# Bus_Definition_V1_22.net
KiCad netlist of a schematic drawn in EAGLE
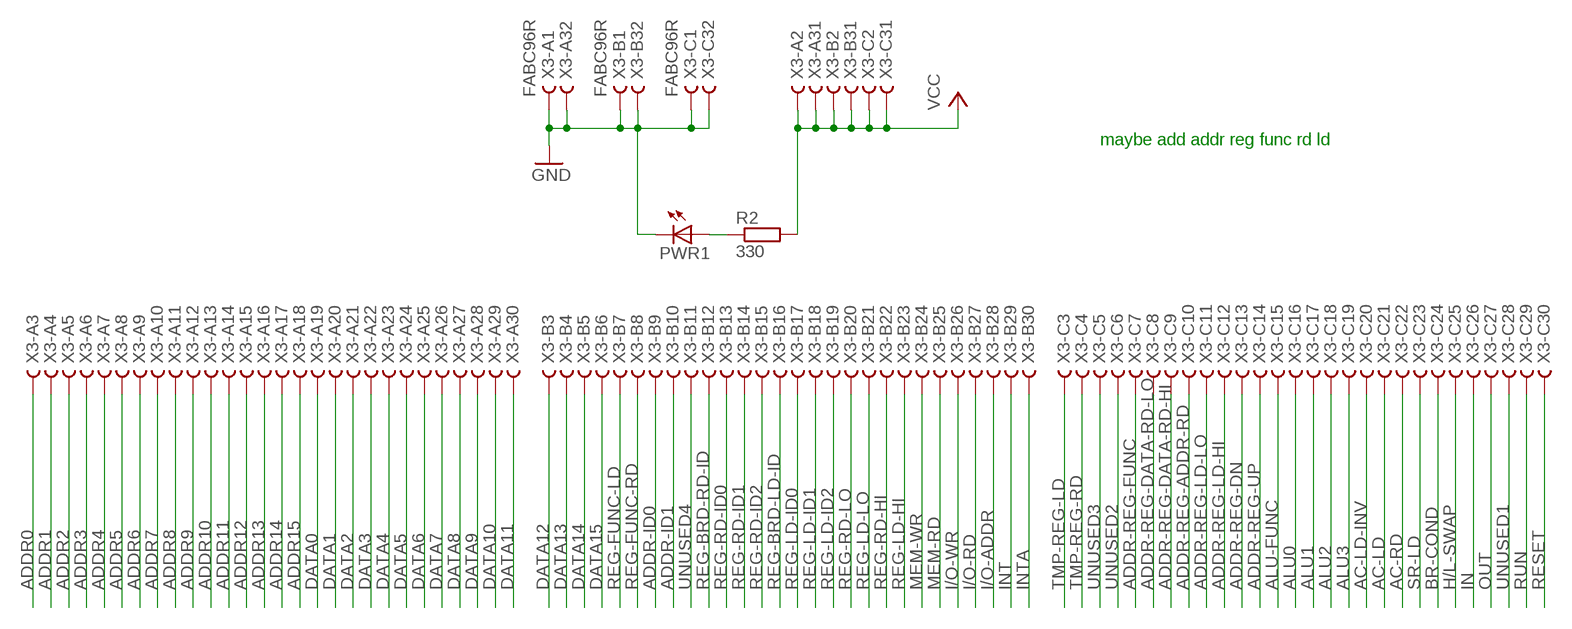
[diagram p0: schematic, sheet 1]

(export (version "E")
  (design (tool "Eeschema 10.0.6"))
  (components
    (comp (ref "PWR1")
      (value "LED5MM")
      (footprint "eagle-import:LED5MM")
      (libsource (lib "eagle-import") (part "LED5MM"))
    )
    (comp (ref "R2")
      (value "330")
      (footprint "eagle-import:0207_10")
      (libsource (lib "eagle-import") (part "R0207/10"))
    )
    (comp (ref "X3")
      (value "FABC96R")
      (footprint "eagle-import:FABC96R")
      (libsource (lib "eagle-import") (part "FABC96R"))
    )
  )
  (nets
    (net (code "1") (name "/AC-LD") (class "Default")
      (node (ref "X3") (pin "C21") (pinfunction "B_C21") (pintype "passive"))
    )
    (net (code "2") (name "/AC-LD-INV") (class "Default")
      (node (ref "X3") (pin "C20") (pinfunction "B_C20") (pintype "passive"))
    )
    (net (code "3") (name "/AC-RD") (class "Default")
      (node (ref "X3") (pin "C22") (pinfunction "B_C22") (pintype "passive"))
    )
    (net (code "4") (name "/ADDR-ID0") (class "Default")
      (node (ref "X3") (pin "B9") (pinfunction "B_B9") (pintype "passive"))
    )
    (net (code "5") (name "/ADDR-ID1") (class "Default")
      (node (ref "X3") (pin "B10") (pinfunction "B_B10") (pintype "passive"))
    )
    (net (code "6") (name "/ADDR-REG-ADDR-RD") (class "Default")
      (node (ref "X3") (pin "C10") (pinfunction "B_C10") (pintype "passive"))
    )
    (net (code "7") (name "/ADDR-REG-DATA-RD-HI") (class "Default")
      (node (ref "X3") (pin "C9") (pinfunction "B_C9") (pintype "passive"))
    )
    (net (code "8") (name "/ADDR-REG-DATA-RD-LO") (class "Default")
      (node (ref "X3") (pin "C8") (pinfunction "B_C8") (pintype "passive"))
    )
    (net (code "9") (name "/ADDR-REG-DN") (class "Default")
      (node (ref "X3") (pin "C13") (pinfunction "B_C13") (pintype "passive"))
    )
    (net (code "10") (name "/ADDR-REG-FUNC") (class "Default")
      (node (ref "X3") (pin "C7") (pinfunction "B_C7") (pintype "passive"))
    )
    (net (code "11") (name "/ADDR-REG-LD-HI") (class "Default")
      (node (ref "X3") (pin "C12") (pinfunction "B_C12") (pintype "passive"))
    )
    (net (code "12") (name "/ADDR-REG-LD-LO") (class "Default")
      (node (ref "X3") (pin "C11") (pinfunction "B_C11") (pintype "passive"))
    )
    (net (code "13") (name "/ADDR-REG-UP") (class "Default")
      (node (ref "X3") (pin "C14") (pinfunction "B_C14") (pintype "passive"))
    )
    (net (code "14") (name "/ADDR0") (class "Default")
      (node (ref "X3") (pin "A3") (pinfunction "B_A3") (pintype "passive"))
    )
    (net (code "15") (name "/ADDR1") (class "Default")
      (node (ref "X3") (pin "A4") (pinfunction "B_A4") (pintype "passive"))
    )
    (net (code "16") (name "/ADDR2") (class "Default")
      (node (ref "X3") (pin "A5") (pinfunction "B_A5") (pintype "passive"))
    )
    (net (code "17") (name "/ADDR3") (class "Default")
      (node (ref "X3") (pin "A6") (pinfunction "B_A6") (pintype "passive"))
    )
    (net (code "18") (name "/ADDR4") (class "Default")
      (node (ref "X3") (pin "A7") (pinfunction "B_A7") (pintype "passive"))
    )
    (net (code "19") (name "/ADDR5") (class "Default")
      (node (ref "X3") (pin "A8") (pinfunction "B_A8") (pintype "passive"))
    )
    (net (code "20") (name "/ADDR6") (class "Default")
      (node (ref "X3") (pin "A9") (pinfunction "B_A9") (pintype "passive"))
    )
    (net (code "21") (name "/ADDR7") (class "Default")
      (node (ref "X3") (pin "A10") (pinfunction "B_A10") (pintype "passive"))
    )
    (net (code "22") (name "/ADDR8") (class "Default")
      (node (ref "X3") (pin "A11") (pinfunction "B_A11") (pintype "passive"))
    )
    (net (code "23") (name "/ADDR9") (class "Default")
      (node (ref "X3") (pin "A12") (pinfunction "B_A12") (pintype "passive"))
    )
    (net (code "24") (name "/ADDR10") (class "Default")
      (node (ref "X3") (pin "A13") (pinfunction "B_A13") (pintype "passive"))
    )
    (net (code "25") (name "/ADDR11") (class "Default")
      (node (ref "X3") (pin "A14") (pinfunction "B_A14") (pintype "passive"))
    )
    (net (code "26") (name "/ADDR12") (class "Default")
      (node (ref "X3") (pin "A15") (pinfunction "B_A15") (pintype "passive"))
    )
    (net (code "27") (name "/ADDR13") (class "Default")
      (node (ref "X3") (pin "A16") (pinfunction "B_A16") (pintype "passive"))
    )
    (net (code "28") (name "/ADDR14") (class "Default")
      (node (ref "X3") (pin "A17") (pinfunction "B_A17") (pintype "passive"))
    )
    (net (code "29") (name "/ADDR15") (class "Default")
      (node (ref "X3") (pin "A18") (pinfunction "B_A18") (pintype "passive"))
    )
    (net (code "30") (name "/ALU-FUNC") (class "Default")
      (node (ref "X3") (pin "C15") (pinfunction "B_C15") (pintype "passive"))
    )
    (net (code "31") (name "/ALU0") (class "Default")
      (node (ref "X3") (pin "C16") (pinfunction "B_C16") (pintype "passive"))
    )
    (net (code "32") (name "/ALU1") (class "Default")
      (node (ref "X3") (pin "C17") (pinfunction "B_C17") (pintype "passive"))
    )
    (net (code "33") (name "/ALU2") (class "Default")
      (node (ref "X3") (pin "C18") (pinfunction "B_C18") (pintype "passive"))
    )
    (net (code "34") (name "/ALU3") (class "Default")
      (node (ref "X3") (pin "C19") (pinfunction "B_C19") (pintype "passive"))
    )
    (net (code "35") (name "/BR-COND") (class "Default")
      (node (ref "X3") (pin "C24") (pinfunction "B_C24") (pintype "passive"))
    )
    (net (code "36") (name "/DATA0") (class "Default")
      (node (ref "X3") (pin "A19") (pinfunction "B_A19") (pintype "passive"))
    )
    (net (code "37") (name "/DATA1") (class "Default")
      (node (ref "X3") (pin "A20") (pinfunction "B_A20") (pintype "passive"))
    )
    (net (code "38") (name "/DATA2") (class "Default")
      (node (ref "X3") (pin "A21") (pinfunction "B_A21") (pintype "passive"))
    )
    (net (code "39") (name "/DATA3") (class "Default")
      (node (ref "X3") (pin "A22") (pinfunction "B_A22") (pintype "passive"))
    )
    (net (code "40") (name "/DATA4") (class "Default")
      (node (ref "X3") (pin "A23") (pinfunction "B_A23") (pintype "passive"))
    )
    (net (code "41") (name "/DATA5") (class "Default")
      (node (ref "X3") (pin "A24") (pinfunction "B_A24") (pintype "passive"))
    )
    (net (code "42") (name "/DATA6") (class "Default")
      (node (ref "X3") (pin "A25") (pinfunction "B_A25") (pintype "passive"))
    )
    (net (code "43") (name "/DATA7") (class "Default")
      (node (ref "X3") (pin "A26") (pinfunction "B_A26") (pintype "passive"))
    )
    (net (code "44") (name "/DATA8") (class "Default")
      (node (ref "X3") (pin "A27") (pinfunction "B_A27") (pintype "passive"))
    )
    (net (code "45") (name "/DATA9") (class "Default")
      (node (ref "X3") (pin "A28") (pinfunction "B_A28") (pintype "passive"))
    )
    (net (code "46") (name "/DATA10") (class "Default")
      (node (ref "X3") (pin "A29") (pinfunction "B_A29") (pintype "passive"))
    )
    (net (code "47") (name "/DATA11") (class "Default")
      (node (ref "X3") (pin "A30") (pinfunction "B_A30") (pintype "passive"))
    )
    (net (code "48") (name "/DATA12") (class "Default")
      (node (ref "X3") (pin "B3") (pinfunction "B_B3") (pintype "passive"))
    )
    (net (code "49") (name "/DATA13") (class "Default")
      (node (ref "X3") (pin "B4") (pinfunction "B_B4") (pintype "passive"))
    )
    (net (code "50") (name "/DATA14") (class "Default")
      (node (ref "X3") (pin "B5") (pinfunction "B_B5") (pintype "passive"))
    )
    (net (code "51") (name "/DATA15") (class "Default")
      (node (ref "X3") (pin "B6") (pinfunction "B_B6") (pintype "passive"))
    )
    (net (code "52") (name "/H{slash}L-SWAP") (class "Default")
      (node (ref "X3") (pin "C25") (pinfunction "B_C25") (pintype "passive"))
    )
    (net (code "53") (name "/IN") (class "Default")
      (node (ref "X3") (pin "C26") (pinfunction "B_C26") (pintype "passive"))
    )
    (net (code "54") (name "/INT") (class "Default")
      (node (ref "X3") (pin "B29") (pinfunction "B_B29") (pintype "passive"))
    )
    (net (code "55") (name "/INTA") (class "Default")
      (node (ref "X3") (pin "B30") (pinfunction "B_B30") (pintype "passive"))
    )
    (net (code "56") (name "/I{slash}O-ADDR") (class "Default")
      (node (ref "X3") (pin "B28") (pinfunction "B_B28") (pintype "passive"))
    )
    (net (code "57") (name "/I{slash}O-RD") (class "Default")
      (node (ref "X3") (pin "B27") (pinfunction "B_B27") (pintype "passive"))
    )
    (net (code "58") (name "/I{slash}O-WR") (class "Default")
      (node (ref "X3") (pin "B26") (pinfunction "B_B26") (pintype "passive"))
    )
    (net (code "59") (name "/MEM-RD") (class "Default")
      (node (ref "X3") (pin "B25") (pinfunction "B_B25") (pintype "passive"))
    )
    (net (code "60") (name "/MEM-WR") (class "Default")
      (node (ref "X3") (pin "B24") (pinfunction "B_B24") (pintype "passive"))
    )
    (net (code "61") (name "/OUT") (class "Default")
      (node (ref "X3") (pin "C27") (pinfunction "B_C27") (pintype "passive"))
    )
    (net (code "62") (name "/REG-BRD-LD-ID") (class "Default")
      (node (ref "X3") (pin "B16") (pinfunction "B_B16") (pintype "passive"))
    )
    (net (code "63") (name "/REG-BRD-RD-ID") (class "Default")
      (node (ref "X3") (pin "B12") (pinfunction "B_B12") (pintype "passive"))
    )
    (net (code "64") (name "/REG-FUNC-LD") (class "Default")
      (node (ref "X3") (pin "B7") (pinfunction "B_B7") (pintype "passive"))
    )
    (net (code "65") (name "/REG-FUNC-RD") (class "Default")
      (node (ref "X3") (pin "B8") (pinfunction "B_B8") (pintype "passive"))
    )
    (net (code "66") (name "/REG-LD-HI") (class "Default")
      (node (ref "X3") (pin "B23") (pinfunction "B_B23") (pintype "passive"))
    )
    (net (code "67") (name "/REG-LD-ID0") (class "Default")
      (node (ref "X3") (pin "B17") (pinfunction "B_B17") (pintype "passive"))
    )
    (net (code "68") (name "/REG-LD-ID1") (class "Default")
      (node (ref "X3") (pin "B18") (pinfunction "B_B18") (pintype "passive"))
    )
    (net (code "69") (name "/REG-LD-ID2") (class "Default")
      (node (ref "X3") (pin "B19") (pinfunction "B_B19") (pintype "passive"))
    )
    (net (code "70") (name "/REG-LD-LO") (class "Default")
      (node (ref "X3") (pin "B21") (pinfunction "B_B21") (pintype "passive"))
    )
    (net (code "71") (name "/REG-RD-HI") (class "Default")
      (node (ref "X3") (pin "B22") (pinfunction "B_B22") (pintype "passive"))
    )
    (net (code "72") (name "/REG-RD-ID0") (class "Default")
      (node (ref "X3") (pin "B13") (pinfunction "B_B13") (pintype "passive"))
    )
    (net (code "73") (name "/REG-RD-ID1") (class "Default")
      (node (ref "X3") (pin "B14") (pinfunction "B_B14") (pintype "passive"))
    )
    (net (code "74") (name "/REG-RD-ID2") (class "Default")
      (node (ref "X3") (pin "B15") (pinfunction "B_B15") (pintype "passive"))
    )
    (net (code "75") (name "/REG-RD-LO") (class "Default")
      (node (ref "X3") (pin "B20") (pinfunction "B_B20") (pintype "passive"))
    )
    (net (code "76") (name "/RESET") (class "Default")
      (node (ref "X3") (pin "C30") (pinfunction "B_C30") (pintype "passive"))
    )
    (net (code "77") (name "/RUN") (class "Default")
      (node (ref "X3") (pin "C29") (pinfunction "B_C29") (pintype "passive"))
    )
    (net (code "78") (name "/SR-LD") (class "Default")
      (node (ref "X3") (pin "C23") (pinfunction "B_C23") (pintype "passive"))
    )
    (net (code "79") (name "/TMP-REG-LD") (class "Default")
      (node (ref "X3") (pin "C3") (pinfunction "B_C3") (pintype "passive"))
    )
    (net (code "80") (name "/TMP-REG-RD") (class "Default")
      (node (ref "X3") (pin "C4") (pinfunction "B_C4") (pintype "passive"))
    )
    (net (code "81") (name "/UNUSED1") (class "Default")
      (node (ref "X3") (pin "C28") (pinfunction "B_C28") (pintype "passive"))
    )
    (net (code "82") (name "/UNUSED2") (class "Default")
      (node (ref "X3") (pin "C6") (pinfunction "B_C6") (pintype "passive"))
    )
    (net (code "83") (name "/UNUSED3") (class "Default")
      (node (ref "X3") (pin "C5") (pinfunction "B_C5") (pintype "passive"))
    )
    (net (code "84") (name "/UNUSED4") (class "Default")
      (node (ref "X3") (pin "B11") (pinfunction "B_B11") (pintype "passive"))
    )
    (net (code "85") (name "GND") (class "Default")
      (node (ref "PWR1") (pin "K") (pinfunction "C_K") (pintype "passive"))
      (node (ref "X3") (pin "A1") (pinfunction "B_A1") (pintype "passive"))
      (node (ref "X3") (pin "A32") (pinfunction "B_A32") (pintype "passive"))
      (node (ref "X3") (pin "B1") (pinfunction "B_B1") (pintype "passive"))
      (node (ref "X3") (pin "B32") (pinfunction "B_B32") (pintype "passive"))
      (node (ref "X3") (pin "C1") (pinfunction "B_C1") (pintype "passive"))
      (node (ref "X3") (pin "C32") (pinfunction "B_C32") (pintype "passive"))
    )
    (net (code "86") (name "Net-(PWR1-PadA)") (class "Default")
      (node (ref "PWR1") (pin "A") (pinfunction "A_A") (pintype "passive"))
      (node (ref "R2") (pin "1") (pinfunction "1_1") (pintype "passive"))
    )
    (net (code "87") (name "VCC") (class "Default")
      (node (ref "R2") (pin "2") (pinfunction "2_2") (pintype "passive"))
      (node (ref "X3") (pin "A2") (pinfunction "B_A2") (pintype "passive"))
      (node (ref "X3") (pin "A31") (pinfunction "B_A31") (pintype "passive"))
      (node (ref "X3") (pin "B2") (pinfunction "B_B2") (pintype "passive"))
      (node (ref "X3") (pin "B31") (pinfunction "B_B31") (pintype "passive"))
      (node (ref "X3") (pin "C2") (pinfunction "B_C2") (pintype "passive"))
      (node (ref "X3") (pin "C31") (pinfunction "B_C31") (pintype "passive"))
    )
  )
)
